# untitled.net
KiCad netlist of a schematic drawn in EAGLE
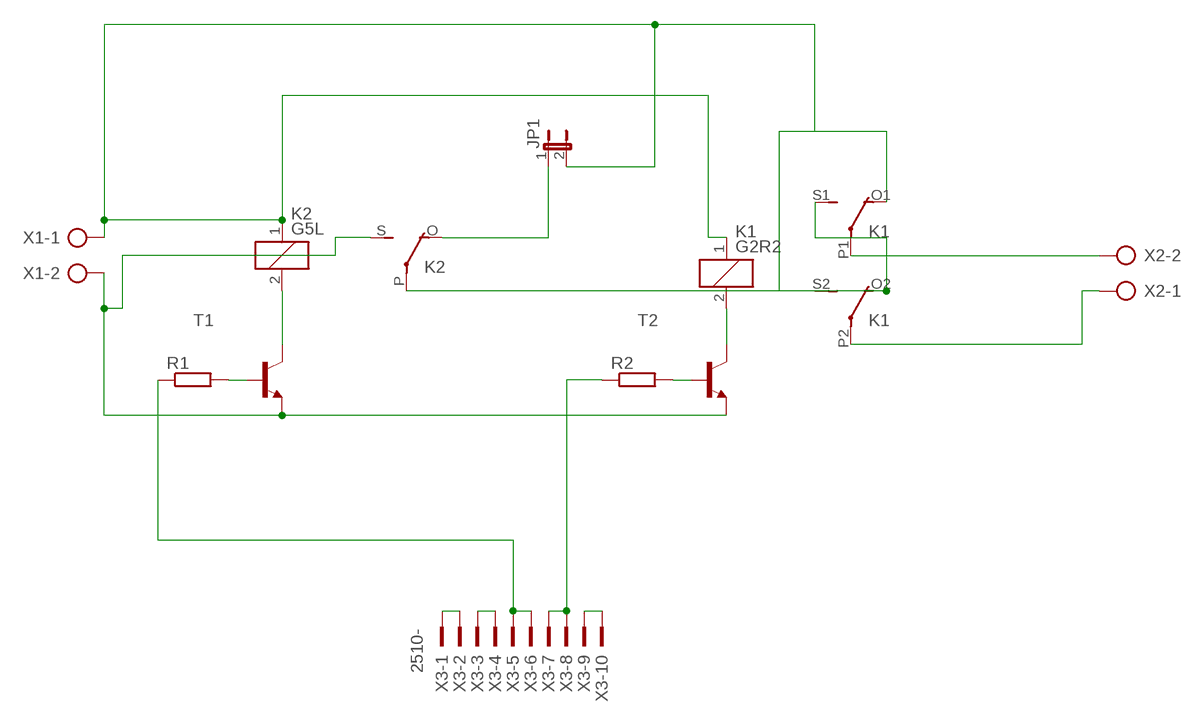
[diagram p0: schematic, sheet 1]

(export (version "E")
  (design (tool "Eeschema 10.0.6"))
  (components
    (comp (ref "JP1")
      (value "JP1E")
      (footprint "eagle-import:JP1")
      (libsource (lib "eagle-import") (part "JP1E"))
    )
    (comp (ref "K1")
      (value "G2R2")
      (footprint "eagle-import:G2R2")
      (fields (field (name "MF") "OMRON COMPONENTS USA") (field (name "MPN") "G2R-2-DC6"))
      (libsource (lib "eagle-import") (part "G2R2"))
    )
    (comp (ref "K2")
      (value "G5L")
      (footprint "eagle-import:G5LE")
      (libsource (lib "eagle-import") (part "G5L"))
    )
    (comp (ref "R1")
      (value "R-EU_0207/10")
      (footprint "eagle-import:0207_10")
      (libsource (lib "eagle-import") (part "R-EU_0207/10"))
    )
    (comp (ref "R2")
      (value "R-EU_0207/10")
      (footprint "eagle-import:0207_10")
      (libsource (lib "eagle-import") (part "R-EU_0207/10"))
    )
    (comp (ref "T1")
      (value "2N6517-NPN-TO92-CBE")
      (footprint "eagle-import:TO92-CBE")
      (libsource (lib "eagle-import") (part "-NPN-TO92-CBE2N6517"))
    )
    (comp (ref "T2")
      (value "2N6517-NPN-TO92-CBE")
      (footprint "eagle-import:TO92-CBE")
      (libsource (lib "eagle-import") (part "-NPN-TO92-CBE2N6517"))
    )
    (comp (ref "X1")
      (value "AK300/2")
      (footprint "eagle-import:AK300_2")
      (libsource (lib "eagle-import") (part "AK300/2"))
    )
    (comp (ref "X2")
      (value "AK300/2")
      (footprint "eagle-import:AK300_2")
      (libsource (lib "eagle-import") (part "AK300/2"))
    )
    (comp (ref "X3")
      (value "2510-")
      (footprint "eagle-import:PAK100_2500-10")
      (fields (field (name "MF") "3M") (field (name "MPN") "2510-6002UB"))
      (libsource (lib "eagle-import") (part "2510-"))
    )
  )
  (nets
    (net (code "1") (name "Net-(JP1-Pad1)") (class "Default")
      (node (ref "JP1") (pin "1") (pinfunction "1_1") (pintype "passive"))
      (node (ref "K2") (pin "O") (pinfunction "O_O") (pintype "passive"))
    )
    (net (code "2") (name "Net-(K1-Pad2)") (class "Default")
      (node (ref "K1") (pin "2") (pinfunction "2_2") (pintype "passive"))
      (node (ref "T2") (pin "C") (pinfunction "C_C") (pintype "passive"))
    )
    (net (code "3") (name "Net-(K1B-O)") (class "Default")
      (node (ref "JP1") (pin "2") (pinfunction "2_2") (pintype "passive"))
      (node (ref "K1") (pin "1") (pinfunction "1_1") (pintype "passive"))
      (node (ref "K1") (pin "O1") (pinfunction "O_O1") (pintype "passive"))
      (node (ref "K1") (pin "S2") (pinfunction "S_S2") (pintype "passive"))
      (node (ref "K2") (pin "1") (pinfunction "1_1") (pintype "passive"))
      (node (ref "X1") (pin "1") (pinfunction "KL_1") (pintype "passive"))
    )
    (net (code "4") (name "Net-(K1B-P)") (class "Default")
      (node (ref "K1") (pin "P1") (pinfunction "P_P1") (pintype "passive"))
      (node (ref "X2") (pin "2") (pinfunction "KL_2") (pintype "passive"))
    )
    (net (code "5") (name "Net-(K1B-S)") (class "Default")
      (node (ref "K1") (pin "O2") (pinfunction "O_O2") (pintype "passive"))
      (node (ref "K1") (pin "S1") (pinfunction "S_S1") (pintype "passive"))
      (node (ref "K2") (pin "P") (pinfunction "P_P") (pintype "passive"))
    )
    (net (code "6") (name "Net-(K1C-P)") (class "Default")
      (node (ref "K1") (pin "P2") (pinfunction "P_P2") (pintype "passive"))
      (node (ref "X2") (pin "1") (pinfunction "KL_1") (pintype "passive"))
    )
    (net (code "7") (name "Net-(K2-Pad2)") (class "Default")
      (node (ref "K2") (pin "2") (pinfunction "2_2") (pintype "passive"))
      (node (ref "T1") (pin "C") (pinfunction "C_C") (pintype "passive"))
    )
    (net (code "8") (name "Net-(R1-Pad2)") (class "Default")
      (node (ref "R1") (pin "2") (pinfunction "2_2") (pintype "passive"))
      (node (ref "T1") (pin "B") (pinfunction "B_B") (pintype "passive"))
    )
    (net (code "9") (name "Net-(R2-Pad2)") (class "Default")
      (node (ref "R2") (pin "2") (pinfunction "2_2") (pintype "passive"))
      (node (ref "T2") (pin "B") (pinfunction "B_B") (pintype "passive"))
    )
    (net (code "10") (name "Net-(X1B-KL)") (class "Default")
      (node (ref "K2") (pin "S") (pinfunction "S_S") (pintype "passive"))
      (node (ref "T1") (pin "E") (pinfunction "E_E") (pintype "passive"))
      (node (ref "T2") (pin "E") (pinfunction "E_E") (pintype "passive"))
      (node (ref "X1") (pin "2") (pinfunction "KL_2") (pintype "passive"))
    )
    (net (code "11") (name "Net-(X3A-KL)") (class "Default")
      (node (ref "X3") (pin "1") (pinfunction "KL_1") (pintype "passive"))
      (node (ref "X3") (pin "2") (pinfunction "KL_2") (pintype "passive"))
    )
    (net (code "12") (name "Net-(X3B-KL)") (class "Default")
      (node (ref "X3") (pin "10") (pinfunction "KL_10") (pintype "passive"))
      (node (ref "X3") (pin "9") (pinfunction "KL_9") (pintype "passive"))
    )
    (net (code "13") (name "Net-(X3D-KL)") (class "Default")
      (node (ref "X3") (pin "3") (pinfunction "KL_3") (pintype "passive"))
      (node (ref "X3") (pin "4") (pinfunction "KL_4") (pintype "passive"))
    )
    (net (code "14") (name "Net-(X3F-KL)") (class "Default")
      (node (ref "R1") (pin "1") (pinfunction "1_1") (pintype "passive"))
      (node (ref "X3") (pin "5") (pinfunction "KL_5") (pintype "passive"))
      (node (ref "X3") (pin "6") (pinfunction "KL_6") (pintype "passive"))
    )
    (net (code "15") (name "Net-(X3H-KL)") (class "Default")
      (node (ref "R2") (pin "1") (pinfunction "1_1") (pintype "passive"))
      (node (ref "X3") (pin "7") (pinfunction "KL_7") (pintype "passive"))
      (node (ref "X3") (pin "8") (pinfunction "KL_8") (pintype "passive"))
    )
  )
)
